# doorbell.net
KiCad netlist of a schematic drawn in EAGLE
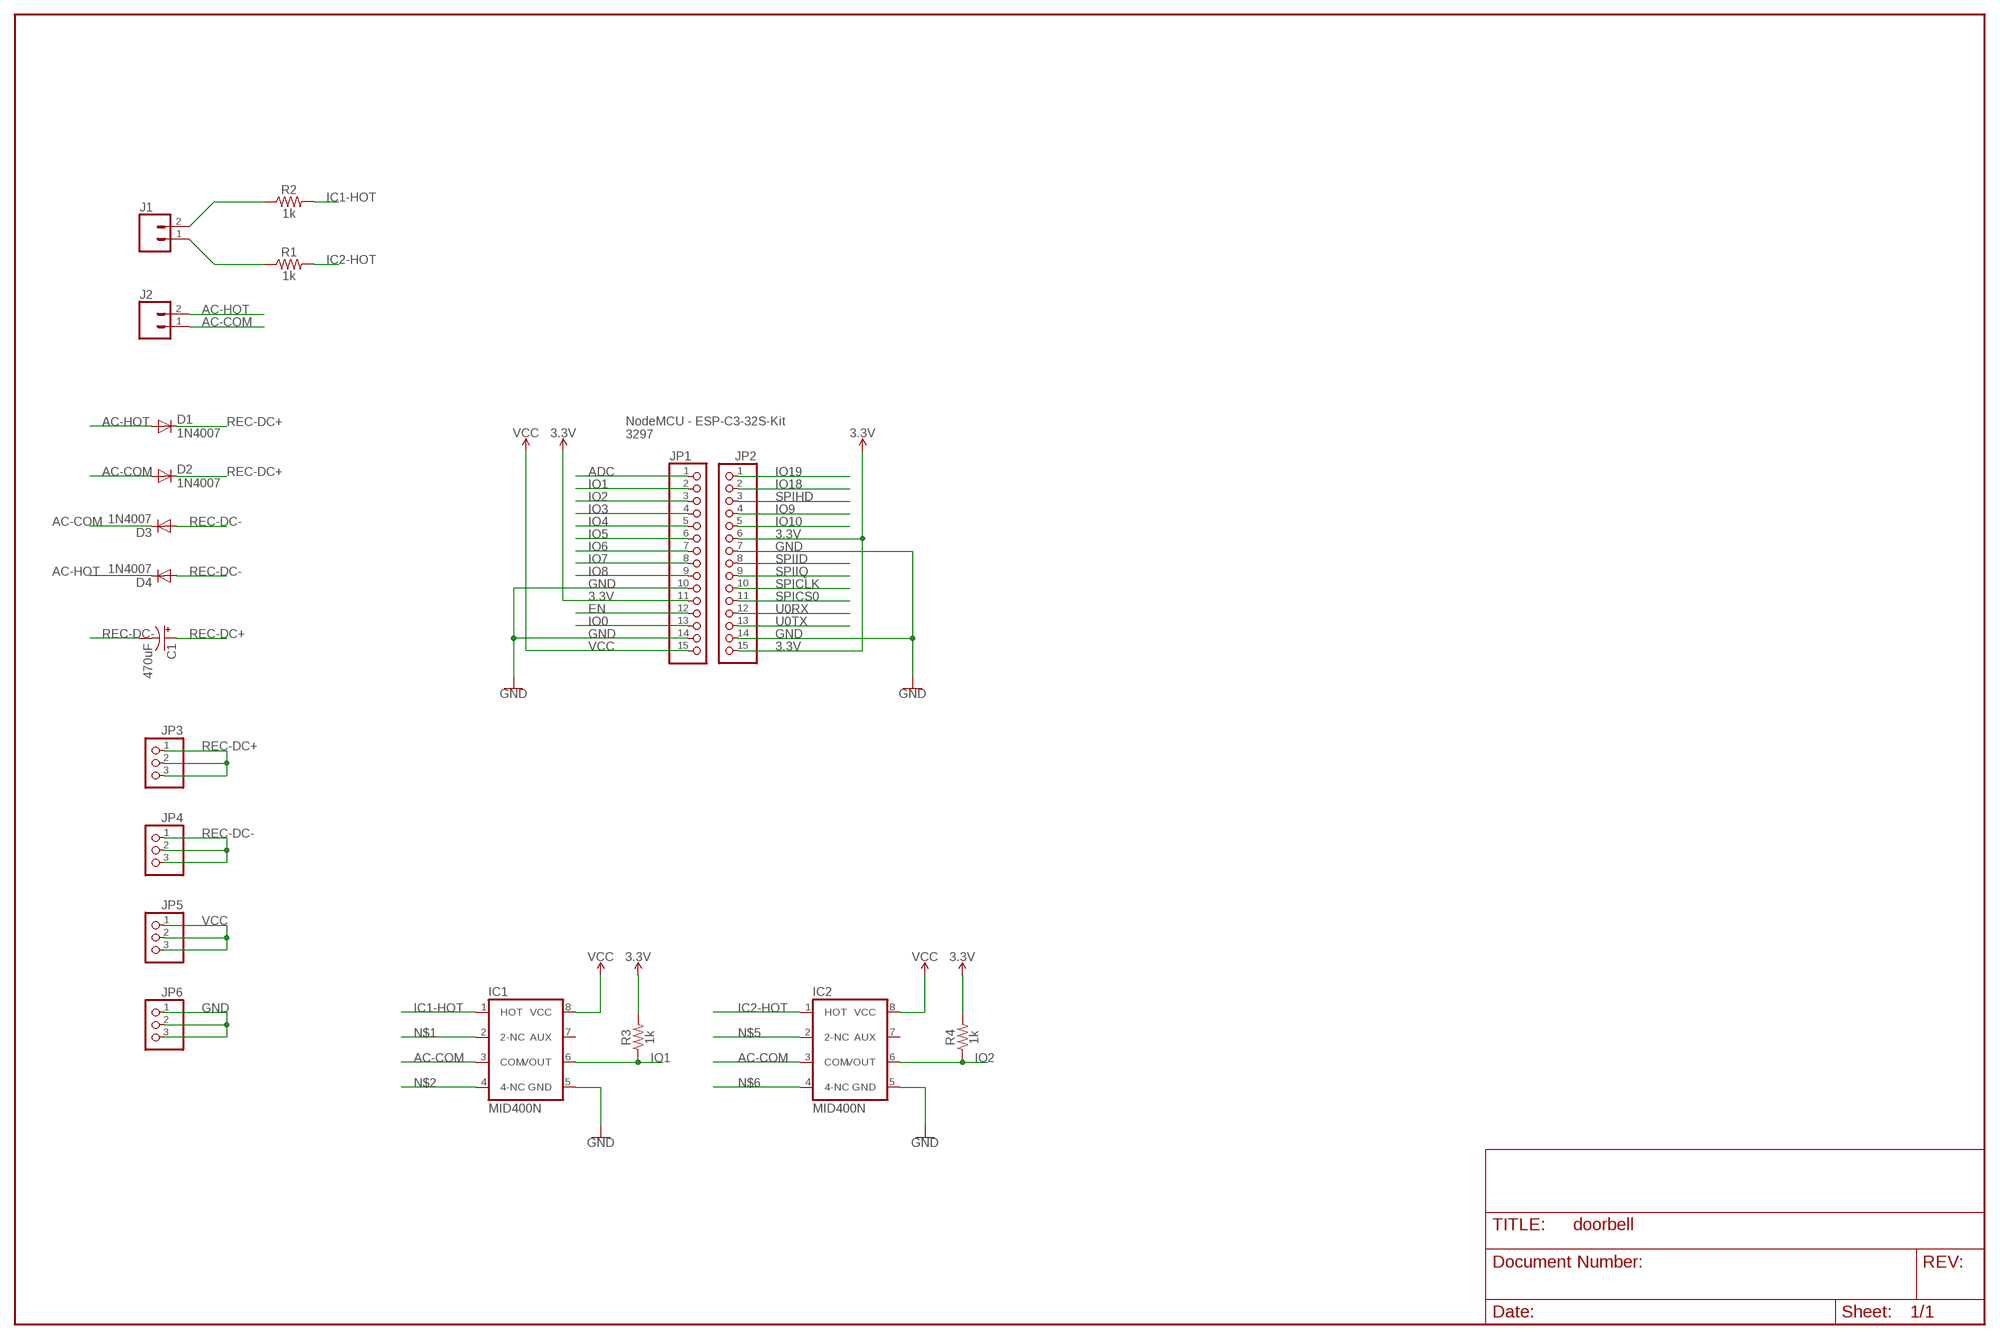
[diagram p0: schematic, sheet 1]

(export (version "E")
  (design (tool "Eeschema 10.0.6"))
  (components
    (comp (ref "C1")
      (value "470uF")
      (footprint "eagle-import:E7,5-18")
      (libsource (lib "eagle-import") (part "CPOL-USE7.5-18"))
    )
    (comp (ref "D1")
      (value "1N4007")
      (footprint "eagle-import:DO41-10")
      (libsource (lib "eagle-import") (part "1N4004"))
    )
    (comp (ref "D2")
      (value "1N4007")
      (footprint "eagle-import:DO41-10")
      (libsource (lib "eagle-import") (part "1N4004"))
    )
    (comp (ref "D3")
      (value "1N4007")
      (footprint "eagle-import:DO41-10")
      (libsource (lib "eagle-import") (part "1N4004"))
    )
    (comp (ref "D4")
      (value "1N4007")
      (footprint "eagle-import:DO41-10")
      (libsource (lib "eagle-import") (part "1N4004"))
    )
    (comp (ref "IC1")
      (value "MID400N")
      (footprint "eagle-import:DIL08-ROUND")
      (libsource (lib "eagle-import") (part "MID400N"))
    )
    (comp (ref "IC2")
      (value "MID400N")
      (footprint "eagle-import:DIL08-ROUND")
      (libsource (lib "eagle-import") (part "MID400N"))
    )
    (comp (ref "J1")
      (value "CONN_023.5MM")
      (footprint "eagle-import:SCREWTERMINAL-3.5MM-2")
      (libsource (lib "eagle-import") (part "CONN_023.5MM"))
    )
    (comp (ref "J2")
      (value "CONN_023.5MM")
      (footprint "eagle-import:SCREWTERMINAL-3.5MM-2")
      (libsource (lib "eagle-import") (part "CONN_023.5MM"))
    )
    (comp (ref "JP1")
      (value "PINHD-1X15")
      (footprint "eagle-import:1X15")
      (libsource (lib "eagle-import") (part "PINHD-1X15"))
    )
    (comp (ref "JP2")
      (value "PINHD-1X15")
      (footprint "eagle-import:1X15")
      (libsource (lib "eagle-import") (part "PINHD-1X15"))
    )
    (comp (ref "JP3")
      (value "PINHD-1X3")
      (footprint "eagle-import:1X03")
      (libsource (lib "eagle-import") (part "PINHD-1X3"))
    )
    (comp (ref "JP4")
      (value "PINHD-1X3")
      (footprint "eagle-import:1X03")
      (libsource (lib "eagle-import") (part "PINHD-1X3"))
    )
    (comp (ref "JP5")
      (value "PINHD-1X3")
      (footprint "eagle-import:1X03")
      (libsource (lib "eagle-import") (part "PINHD-1X3"))
    )
    (comp (ref "JP6")
      (value "PINHD-1X3")
      (footprint "eagle-import:1X03")
      (libsource (lib "eagle-import") (part "PINHD-1X3"))
    )
    (comp (ref "R1")
      (value "1k")
      (footprint "eagle-import:AXIAL-0.3")
      (libsource (lib "eagle-import") (part "1KOHM-HORIZ-1/4W-1%"))
    )
    (comp (ref "R2")
      (value "1k")
      (footprint "eagle-import:AXIAL-0.3")
      (libsource (lib "eagle-import") (part "1KOHM-HORIZ-1/4W-1%"))
    )
    (comp (ref "R3")
      (value "1k")
      (footprint "eagle-import:AXIAL-0.3")
      (libsource (lib "eagle-import") (part "1KOHM-HORIZ-1/4W-1%"))
    )
    (comp (ref "R4")
      (value "1k")
      (footprint "eagle-import:AXIAL-0.3")
      (libsource (lib "eagle-import") (part "1KOHM-HORIZ-1/4W-1%"))
    )
  )
  (nets
    (net (code "1") (name "/AC-COM") (class "Default")
      (node (ref "D2") (pin "A") (pinfunction "A_A") (pintype "passive"))
      (node (ref "D3") (pin "C") (pinfunction "C_C") (pintype "passive"))
      (node (ref "IC1") (pin "3") (pinfunction "COM_3") (pintype "input"))
      (node (ref "IC2") (pin "3") (pinfunction "COM_3") (pintype "input"))
      (node (ref "J2") (pin "1") (pinfunction "1_1") (pintype "passive"))
    )
    (net (code "2") (name "/AC-HOT") (class "Default")
      (node (ref "D1") (pin "A") (pinfunction "A_A") (pintype "passive"))
      (node (ref "D4") (pin "C") (pinfunction "C_C") (pintype "passive"))
      (node (ref "J2") (pin "2") (pinfunction "2_2") (pintype "passive"))
    )
    (net (code "3") (name "/ADC") (class "Default")
      (node (ref "JP1") (pin "1") (pinfunction "1_1") (pintype "passive"))
    )
    (net (code "4") (name "/EN") (class "Default")
      (node (ref "JP1") (pin "12") (pinfunction "12_12") (pintype "passive"))
    )
    (net (code "5") (name "/IC1-HOT") (class "Default")
      (node (ref "IC1") (pin "1") (pinfunction "HOT_1") (pintype "input"))
      (node (ref "R2") (pin "P$2") (pinfunction "2_P$2") (pintype "passive"))
    )
    (net (code "6") (name "/IC2-HOT") (class "Default")
      (node (ref "IC2") (pin "1") (pinfunction "HOT_1") (pintype "input"))
      (node (ref "R1") (pin "P$2") (pinfunction "2_P$2") (pintype "passive"))
    )
    (net (code "7") (name "/IO0") (class "Default")
      (node (ref "JP1") (pin "13") (pinfunction "13_13") (pintype "passive"))
    )
    (net (code "8") (name "/IO1") (class "Default")
      (node (ref "IC1") (pin "6") (pinfunction "VOUT_6") (pintype "input"))
      (node (ref "JP1") (pin "2") (pinfunction "2_2") (pintype "passive"))
      (node (ref "R3") (pin "P$1") (pinfunction "1_P$1") (pintype "passive"))
    )
    (net (code "9") (name "/IO2") (class "Default")
      (node (ref "IC2") (pin "6") (pinfunction "VOUT_6") (pintype "input"))
      (node (ref "JP1") (pin "3") (pinfunction "3_3") (pintype "passive"))
      (node (ref "R4") (pin "P$1") (pinfunction "1_P$1") (pintype "passive"))
    )
    (net (code "10") (name "/IO3") (class "Default")
      (node (ref "JP1") (pin "4") (pinfunction "4_4") (pintype "passive"))
    )
    (net (code "11") (name "/IO4") (class "Default")
      (node (ref "JP1") (pin "5") (pinfunction "5_5") (pintype "passive"))
    )
    (net (code "12") (name "/IO5") (class "Default")
      (node (ref "JP1") (pin "6") (pinfunction "6_6") (pintype "passive"))
    )
    (net (code "13") (name "/IO6") (class "Default")
      (node (ref "JP1") (pin "7") (pinfunction "7_7") (pintype "passive"))
    )
    (net (code "14") (name "/IO7") (class "Default")
      (node (ref "JP1") (pin "8") (pinfunction "8_8") (pintype "passive"))
    )
    (net (code "15") (name "/IO8") (class "Default")
      (node (ref "JP1") (pin "9") (pinfunction "9_9") (pintype "passive"))
    )
    (net (code "16") (name "/IO9") (class "Default")
      (node (ref "JP2") (pin "4") (pinfunction "4_4") (pintype "passive"))
    )
    (net (code "17") (name "/IO10") (class "Default")
      (node (ref "JP2") (pin "5") (pinfunction "5_5") (pintype "passive"))
    )
    (net (code "18") (name "/IO18") (class "Default")
      (node (ref "JP2") (pin "2") (pinfunction "2_2") (pintype "passive"))
    )
    (net (code "19") (name "/IO19") (class "Default")
      (node (ref "JP2") (pin "1") (pinfunction "1_1") (pintype "passive"))
    )
    (net (code "20") (name "/N$1") (class "Default")
      (node (ref "IC1") (pin "2") (pinfunction "2-NC_2") (pintype "input"))
    )
    (net (code "21") (name "/N$2") (class "Default")
      (node (ref "IC1") (pin "4") (pinfunction "4-NC_4") (pintype "power_in"))
    )
    (net (code "22") (name "/N$5") (class "Default")
      (node (ref "IC2") (pin "2") (pinfunction "2-NC_2") (pintype "input"))
    )
    (net (code "23") (name "/N$6") (class "Default")
      (node (ref "IC2") (pin "4") (pinfunction "4-NC_4") (pintype "power_in"))
    )
    (net (code "24") (name "/REC-DC+") (class "Default")
      (node (ref "C1") (pin "+") (pinfunction "+_+") (pintype "passive"))
      (node (ref "D1") (pin "C") (pinfunction "C_C") (pintype "passive"))
      (node (ref "D2") (pin "C") (pinfunction "C_C") (pintype "passive"))
      (node (ref "JP3") (pin "1") (pinfunction "1_1") (pintype "passive"))
      (node (ref "JP3") (pin "2") (pinfunction "2_2") (pintype "passive"))
      (node (ref "JP3") (pin "3") (pinfunction "3_3") (pintype "passive"))
    )
    (net (code "25") (name "/REC-DC-") (class "Default")
      (node (ref "C1") (pin "-") (pinfunction "-_-") (pintype "passive"))
      (node (ref "D3") (pin "A") (pinfunction "A_A") (pintype "passive"))
      (node (ref "D4") (pin "A") (pinfunction "A_A") (pintype "passive"))
      (node (ref "JP4") (pin "1") (pinfunction "1_1") (pintype "passive"))
      (node (ref "JP4") (pin "2") (pinfunction "2_2") (pintype "passive"))
      (node (ref "JP4") (pin "3") (pinfunction "3_3") (pintype "passive"))
    )
    (net (code "26") (name "/SPICLK") (class "Default")
      (node (ref "JP2") (pin "10") (pinfunction "10_10") (pintype "passive"))
    )
    (net (code "27") (name "/SPICS0") (class "Default")
      (node (ref "JP2") (pin "11") (pinfunction "11_11") (pintype "passive"))
    )
    (net (code "28") (name "/SPIHD") (class "Default")
      (node (ref "JP2") (pin "3") (pinfunction "3_3") (pintype "passive"))
    )
    (net (code "29") (name "/SPIID") (class "Default")
      (node (ref "JP2") (pin "8") (pinfunction "8_8") (pintype "passive"))
    )
    (net (code "30") (name "/SPIIQ") (class "Default")
      (node (ref "JP2") (pin "9") (pinfunction "9_9") (pintype "passive"))
    )
    (net (code "31") (name "/U0RX") (class "Default")
      (node (ref "JP2") (pin "12") (pinfunction "12_12") (pintype "passive"))
    )
    (net (code "32") (name "/U0TX") (class "Default")
      (node (ref "JP2") (pin "13") (pinfunction "13_13") (pintype "passive"))
    )
    (net (code "33") (name "3.3V") (class "Default")
      (node (ref "JP1") (pin "11") (pinfunction "11_11") (pintype "passive"))
      (node (ref "JP2") (pin "15") (pinfunction "15_15") (pintype "passive"))
      (node (ref "JP2") (pin "6") (pinfunction "6_6") (pintype "passive"))
      (node (ref "R3") (pin "P$2") (pinfunction "2_P$2") (pintype "passive"))
      (node (ref "R4") (pin "P$2") (pinfunction "2_P$2") (pintype "passive"))
    )
    (net (code "34") (name "GND") (class "Default")
      (node (ref "IC1") (pin "5") (pinfunction "GND_5") (pintype "power_in"))
      (node (ref "IC2") (pin "5") (pinfunction "GND_5") (pintype "power_in"))
      (node (ref "JP1") (pin "10") (pinfunction "10_10") (pintype "passive"))
      (node (ref "JP1") (pin "14") (pinfunction "14_14") (pintype "passive"))
      (node (ref "JP2") (pin "14") (pinfunction "14_14") (pintype "passive"))
      (node (ref "JP2") (pin "7") (pinfunction "7_7") (pintype "passive"))
      (node (ref "JP6") (pin "1") (pinfunction "1_1") (pintype "passive"))
      (node (ref "JP6") (pin "2") (pinfunction "2_2") (pintype "passive"))
      (node (ref "JP6") (pin "3") (pinfunction "3_3") (pintype "passive"))
    )
    (net (code "35") (name "Net-(R1-1)") (class "Default")
      (node (ref "J1") (pin "1") (pinfunction "1_1") (pintype "passive"))
      (node (ref "R1") (pin "P$1") (pinfunction "1_P$1") (pintype "passive"))
    )
    (net (code "36") (name "Net-(R2-1)") (class "Default")
      (node (ref "J1") (pin "2") (pinfunction "2_2") (pintype "passive"))
      (node (ref "R2") (pin "P$1") (pinfunction "1_P$1") (pintype "passive"))
    )
    (net (code "37") (name "VCC") (class "Default")
      (node (ref "IC1") (pin "8") (pinfunction "VCC_8") (pintype "output"))
      (node (ref "IC2") (pin "8") (pinfunction "VCC_8") (pintype "output"))
      (node (ref "JP1") (pin "15") (pinfunction "15_15") (pintype "passive"))
      (node (ref "JP5") (pin "1") (pinfunction "1_1") (pintype "passive"))
      (node (ref "JP5") (pin "2") (pinfunction "2_2") (pintype "passive"))
      (node (ref "JP5") (pin "3") (pinfunction "3_3") (pintype "passive"))
    )
    (net (code "38") (name "unconnected-(IC1-AUX-Pad7)") (class "Default")
      (node (ref "IC1") (pin "7") (pinfunction "AUX_7") (pintype "input"))
    )
    (net (code "39") (name "unconnected-(IC2-AUX-Pad7)") (class "Default")
      (node (ref "IC2") (pin "7") (pinfunction "AUX_7") (pintype "input"))
    )
  )
)
